# PRG_APT.net
KiCad netlist of a schematic drawn in EAGLE
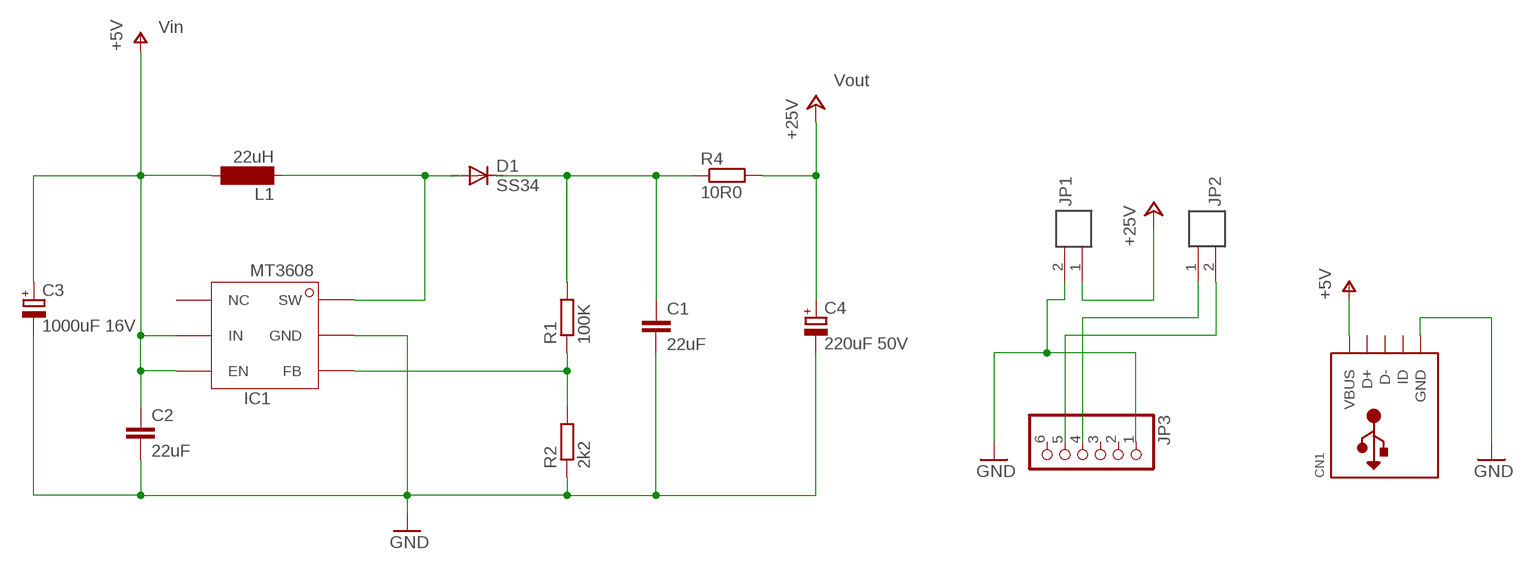
[diagram p0: schematic, sheet 1]

(export (version "E")
  (design (tool "Eeschema 10.0.6"))
  (components
    (comp (ref "C1")
      (value "22uF")
      (footprint "eagle-import:C0805")
      (libsource (lib "eagle-import") (part "C-EUC0805"))
    )
    (comp (ref "C2")
      (value "22uF")
      (footprint "eagle-import:C0805")
      (libsource (lib "eagle-import") (part "C-EUC0805"))
    )
    (comp (ref "C3")
      (value "1000uF 16V")
      (footprint "eagle-import:153CLV-0810")
      (libsource (lib "eagle-import") (part "CPOL-EU153CLV-0810"))
    )
    (comp (ref "C4")
      (value "220uF 50V")
      (footprint "eagle-import:153CLV-1010")
      (libsource (lib "eagle-import") (part "CPOL-EU153CLV-1010"))
    )
    (comp (ref "CN1")
      (value "USBMINIB")
      (footprint "eagle-import:USB-MINIB")
      (libsource (lib "eagle-import") (part "USBMINIB"))
    )
    (comp (ref "D1")
      (value "SS34")
      (footprint "eagle-import:DO-214AC")
      (libsource (lib "eagle-import") (part "DIODE-DO-214AC"))
    )
    (comp (ref "IC1")
      (value "MT3608SOT23-6")
      (footprint "eagle-import:SOT23-6")
      (libsource (lib "eagle-import") (part "MT3608SOT23-6"))
    )
    (comp (ref "JP1")
      (value "ARK254-2")
      (footprint "eagle-import:ARK254-2")
      (libsource (lib "eagle-import") (part "ARK254-2"))
    )
    (comp (ref "JP2")
      (value "ARK254-2")
      (footprint "eagle-import:ARK254-2")
      (libsource (lib "eagle-import") (part "ARK254-2"))
    )
    (comp (ref "JP3")
      (value "PINHD-1X6")
      (footprint "eagle-import:1X06")
      (libsource (lib "eagle-import") (part "PINHD-1X6"))
    )
    (comp (ref "L1")
      (value "22uH")
      (footprint "eagle-import:SLF12555T-102MR34-PF")
      (libsource (lib "eagle-import") (part "SLF12555T-102MR34-PF"))
    )
    (comp (ref "R1")
      (value "100K")
      (footprint "eagle-import:R0805")
      (libsource (lib "eagle-import") (part "R-EU_R0805"))
    )
    (comp (ref "R2")
      (value "2k2")
      (footprint "eagle-import:R0805")
      (libsource (lib "eagle-import") (part "R-EU_R0805"))
    )
    (comp (ref "R4")
      (value "10R0")
      (footprint "eagle-import:M1206")
      (libsource (lib "eagle-import") (part "R-EU_M1206"))
    )
  )
  (nets
    (net (code "1") (name "+5V") (class "Default")
      (node (ref "C2") (pin "1") (pinfunction "1_1") (pintype "passive"))
      (node (ref "C3") (pin "+") (pinfunction "+_+") (pintype "passive"))
      (node (ref "CN1") (pin "VBUS") (pinfunction "VBUS_VBUS") (pintype "power_in"))
      (node (ref "IC1") (pin "P$4") (pinfunction "EN_P$4") (pintype "bidirectional"))
      (node (ref "IC1") (pin "P$5") (pinfunction "IN_P$5") (pintype "bidirectional"))
      (node (ref "L1") (pin "P$2") (pinfunction "2_P$2") (pintype "passive"))
    )
    (net (code "2") (name "+25V") (class "Default")
      (node (ref "C4") (pin "+") (pinfunction "+_+") (pintype "passive"))
      (node (ref "JP1") (pin "1") (pinfunction "1_1") (pintype "bidirectional"))
      (node (ref "R4") (pin "2") (pinfunction "2_2") (pintype "passive"))
    )
    (net (code "3") (name "GND") (class "Default")
      (node (ref "C1") (pin "2") (pinfunction "2_2") (pintype "passive"))
      (node (ref "C2") (pin "2") (pinfunction "2_2") (pintype "passive"))
      (node (ref "C3") (pin "-") (pinfunction "-_-") (pintype "passive"))
      (node (ref "C4") (pin "-") (pinfunction "-_-") (pintype "passive"))
      (node (ref "CN1") (pin "GND") (pinfunction "GND_GND") (pintype "power_in"))
      (node (ref "IC1") (pin "P$2") (pinfunction "GND_P$2") (pintype "bidirectional"))
      (node (ref "JP1") (pin "2") (pinfunction "2_2") (pintype "bidirectional"))
      (node (ref "JP3") (pin "1") (pinfunction "1_1") (pintype "passive"))
      (node (ref "R2") (pin "1") (pinfunction "1_1") (pintype "passive"))
    )
    (net (code "4") (name "Net-(C1-Pad1)") (class "Default")
      (node (ref "C1") (pin "1") (pinfunction "1_1") (pintype "passive"))
      (node (ref "D1") (pin "C") (pinfunction "C_C") (pintype "passive"))
      (node (ref "R1") (pin "2") (pinfunction "2_2") (pintype "passive"))
      (node (ref "R4") (pin "1") (pinfunction "1_1") (pintype "passive"))
    )
    (net (code "5") (name "Net-(IC1-FB)") (class "Default")
      (node (ref "IC1") (pin "P$3") (pinfunction "FB_P$3") (pintype "bidirectional"))
      (node (ref "R1") (pin "1") (pinfunction "1_1") (pintype "passive"))
      (node (ref "R2") (pin "2") (pinfunction "2_2") (pintype "passive"))
    )
    (net (code "6") (name "Net-(IC1-SW)") (class "Default")
      (node (ref "D1") (pin "A") (pinfunction "A_A") (pintype "passive"))
      (node (ref "IC1") (pin "P$1") (pinfunction "SW_P$1") (pintype "bidirectional"))
      (node (ref "L1") (pin "P$1") (pinfunction "1_P$1") (pintype "passive"))
    )
    (net (code "7") (name "Net-(JP2-Pad1)") (class "Default")
      (node (ref "JP2") (pin "1") (pinfunction "1_1") (pintype "bidirectional"))
      (node (ref "JP3") (pin "4") (pinfunction "4_4") (pintype "passive"))
    )
    (net (code "8") (name "Net-(JP2-Pad2)") (class "Default")
      (node (ref "JP2") (pin "2") (pinfunction "2_2") (pintype "bidirectional"))
      (node (ref "JP3") (pin "5") (pinfunction "5_5") (pintype "passive"))
    )
    (net (code "9") (name "unconnected-(CN1-PadD+)") (class "Default")
      (node (ref "CN1") (pin "D+") (pinfunction "D+_D+") (pintype "bidirectional"))
    )
    (net (code "10") (name "unconnected-(CN1-PadD-)") (class "Default")
      (node (ref "CN1") (pin "D-") (pinfunction "D-_D-") (pintype "bidirectional"))
    )
    (net (code "11") (name "unconnected-(CN1-PadID)") (class "Default")
      (node (ref "CN1") (pin "ID") (pinfunction "ID_ID") (pintype "bidirectional"))
    )
    (net (code "12") (name "unconnected-(IC1-NC-PadP$6)") (class "Default")
      (node (ref "IC1") (pin "P$6") (pinfunction "NC_P$6") (pintype "bidirectional"))
    )
    (net (code "13") (name "unconnected-(JP3-Pad2)") (class "Default")
      (node (ref "JP3") (pin "2") (pinfunction "2_2") (pintype "passive"))
    )
    (net (code "14") (name "unconnected-(JP3-Pad3)") (class "Default")
      (node (ref "JP3") (pin "3") (pinfunction "3_3") (pintype "passive"))
    )
    (net (code "15") (name "unconnected-(JP3-Pad6)") (class "Default")
      (node (ref "JP3") (pin "6") (pinfunction "6_6") (pintype "passive"))
    )
  )
)
